# Ethernet.net
KiCad netlist of a schematic drawn in Altium Designer
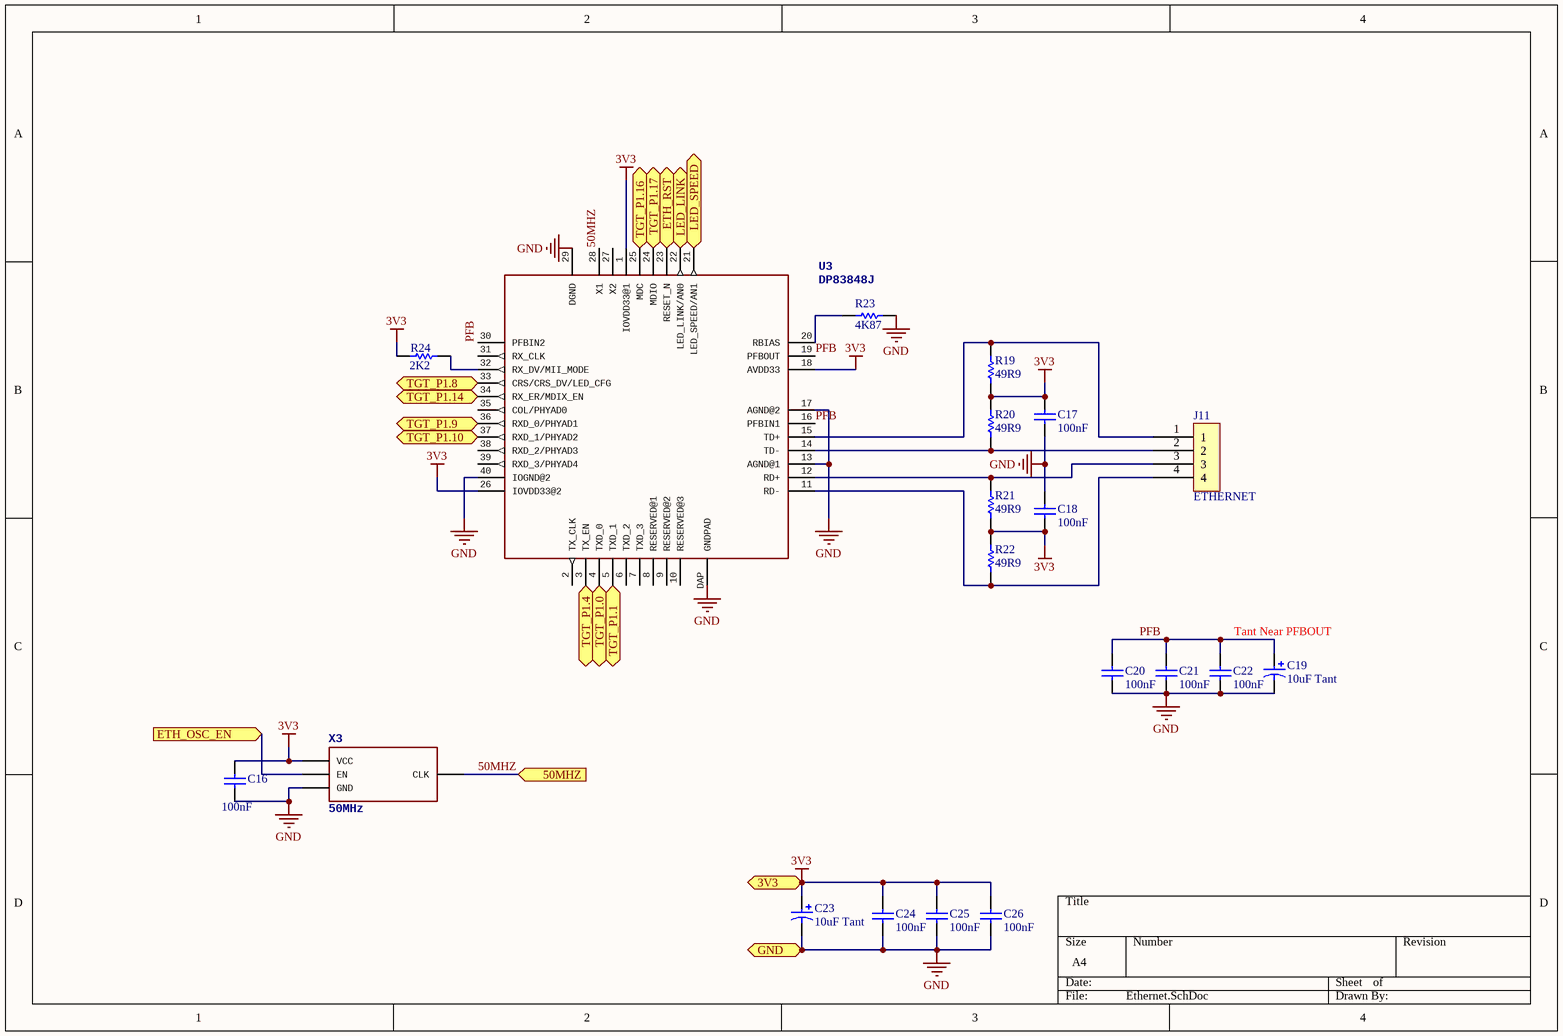
[diagram p0: Ethernet.SchDoc]

(export (version "E")
  (design (tool "Eeschema 10.0.6"))
  (components
    (comp (ref "C16")
      (value "100nF")
      (footprint "CAPC0603(1608)100_L")
      (description "CAP 100nF 6.3V ±5% 0603 (1608 Metric) Thickness 1mm SMD")
      (fields (field (name "TOLERANCE") "Â±5%"))
      (libsource (lib "Altium Content Vault") (part "CMP-1035-02575-1"))
    )
    (comp (ref "C17")
      (value "100nF")
      (footprint "CAPC0603(1608)100_L")
      (description "CAP 100nF 6.3V ±5% 0603 (1608 Metric) Thickness 1mm SMD")
      (fields (field (name "TOLERANCE") "Â±5%"))
      (libsource (lib "Altium Content Vault") (part "CMP-1035-02575-1"))
    )
    (comp (ref "C18")
      (value "100nF")
      (footprint "CAPC0603(1608)100_L")
      (description "CAP 100nF 6.3V ±5% 0603 (1608 Metric) Thickness 1mm SMD")
      (fields (field (name "TOLERANCE") "Â±5%"))
      (libsource (lib "Altium Content Vault") (part "CMP-1035-02575-1"))
    )
    (comp (ref "C19")
      (value "10uF Tant")
      (footprint "CAPMP3528X12N")
      (libsource (lib "passive") (part "cap_pol"))
    )
    (comp (ref "C20")
      (value "100nF")
      (footprint "CAPC0603(1608)100_L")
      (description "CAP 100nF 6.3V ±5% 0603 (1608 Metric) Thickness 1mm SMD")
      (fields (field (name "TOLERANCE") "Â±5%"))
      (libsource (lib "Altium Content Vault") (part "CMP-1035-02575-1"))
    )
    (comp (ref "C21")
      (value "100nF")
      (footprint "CAPC0603(1608)100_L")
      (description "CAP 100nF 6.3V ±5% 0603 (1608 Metric) Thickness 1mm SMD")
      (fields (field (name "TOLERANCE") "Â±5%"))
      (libsource (lib "Altium Content Vault") (part "CMP-1035-02575-1"))
    )
    (comp (ref "C22")
      (value "100nF")
      (footprint "CAPC0603(1608)100_L")
      (description "CAP 100nF 6.3V ±5% 0603 (1608 Metric) Thickness 1mm SMD")
      (fields (field (name "TOLERANCE") "Â±5%"))
      (libsource (lib "Altium Content Vault") (part "CMP-1035-02575-1"))
    )
    (comp (ref "C23")
      (value "10uF Tant")
      (footprint "CAPMP3528X12N")
      (libsource (lib "passive") (part "cap_pol"))
    )
    (comp (ref "C24")
      (value "100nF")
      (footprint "CAPC0603(1608)100_L")
      (description "CAP 100nF 6.3V ±5% 0603 (1608 Metric) Thickness 1mm SMD")
      (fields (field (name "TOLERANCE") "Â±5%"))
      (libsource (lib "Altium Content Vault") (part "CMP-1035-02575-1"))
    )
    (comp (ref "C25")
      (value "100nF")
      (footprint "CAPC0603(1608)100_L")
      (description "CAP 100nF 6.3V ±5% 0603 (1608 Metric) Thickness 1mm SMD")
      (fields (field (name "TOLERANCE") "Â±5%"))
      (libsource (lib "Altium Content Vault") (part "CMP-1035-02575-1"))
    )
    (comp (ref "C26")
      (value "100nF")
      (footprint "CAPC0603(1608)100_L")
      (description "CAP 100nF 6.3V ±5% 0603 (1608 Metric) Thickness 1mm SMD")
      (fields (field (name "TOLERANCE") "Â±5%"))
      (libsource (lib "Altium Content Vault") (part "CMP-1035-02575-1"))
    )
    (comp (ref "J11")
      (value "ETHERNET")
      (footprint "MICRO-MATCH-4")
      (libsource (lib "connectors") (part "HEADER-4"))
    )
    (comp (ref "R19")
      (value "49R9")
      (footprint "RESC0603(1608)_L")
      (description "49R9 0.1W 1% 0603 (1608 Metric)  SMD")
      (fields (field (name "POWER") "0.1 W") (field (name "TOLERANCE") "1 %"))
      (libsource (lib "Altium Content Vault") (part "CMP-1012-00363-1"))
    )
    (comp (ref "R20")
      (value "49R9")
      (footprint "RESC0603(1608)_L")
      (description "49R9 0.1W 1% 0603 (1608 Metric)  SMD")
      (fields (field (name "POWER") "0.1 W") (field (name "TOLERANCE") "1 %"))
      (libsource (lib "Altium Content Vault") (part "CMP-1012-00363-1"))
    )
    (comp (ref "R21")
      (value "49R9")
      (footprint "RESC0603(1608)_L")
      (description "49R9 0.1W 1% 0603 (1608 Metric)  SMD")
      (fields (field (name "POWER") "0.1 W") (field (name "TOLERANCE") "1 %"))
      (libsource (lib "Altium Content Vault") (part "CMP-1012-00363-1"))
    )
    (comp (ref "R22")
      (value "49R9")
      (footprint "RESC0603(1608)_L")
      (description "49R9 0.1W 1% 0603 (1608 Metric)  SMD")
      (fields (field (name "POWER") "0.1 W") (field (name "TOLERANCE") "1 %"))
      (libsource (lib "Altium Content Vault") (part "CMP-1012-00363-1"))
    )
    (comp (ref "R23")
      (value "4K87")
      (footprint "RESC0603(1608)_L")
      (description "4K87 0.1W 1% 0603 (1608 Metric)  SMD")
      (fields (field (name "POWER") "0.1 W") (field (name "TOLERANCE") "1 %"))
      (libsource (lib "Altium Content Vault") (part "CMP-1012-00588-1"))
    )
    (comp (ref "R24")
      (value "2K2")
      (footprint "RESC0603(1608)_L")
      (description "2K2 0.1W 1% 0603 (1608 Metric)  SMD")
      (fields (field (name "TOLERANCE") "1 %") (field (name "POWER") "0.1 W"))
      (libsource (lib "Altium Content Vault") (part "CMP-1012-00546-1"))
    )
    (comp (ref "U3") (value "DP83848J") (footprint "LLP-40") (libsource (lib "mbed-HDK") (part "DP83848J")))
    (comp (ref "X3") (value "50MHz") (footprint "3.2X.2.5") (libsource (lib "mbed-HDK") (part "OSCILLATOR")))
  )
  (nets
    (net (code "1") (name "/50MHZ") (class "Default")
      (node (ref "U3") (pin "28") (pinfunction "X1_28") (pintype "passive"))
      (node (ref "X3") (pin "P$3") (pinfunction "CLK_P$3") (pintype "passive"))
    )
    (net (code "2") (name "/ETH_OSC_EN") (class "Default")
      (node (ref "X3") (pin "P$1") (pinfunction "EN_P$1") (pintype "passive"))
    )
    (net (code "3") (name "/ETH_RST") (class "Default")
      (node (ref "U3") (pin "23") (pinfunction "RESET_N_23") (pintype "passive"))
    )
    (net (code "4") (name "/LED_LINK") (class "Default")
      (node (ref "U3") (pin "22") (pinfunction "LED_LINK/AN0_22") (pintype "output"))
    )
    (net (code "5") (name "/LED_SPEED") (class "Default")
      (node (ref "U3") (pin "21") (pinfunction "LED_SPEED/AN1_21") (pintype "output"))
    )
    (net (code "6") (name "/PFB") (class "Default")
      (node (ref "C19") (pin "2") (pinfunction "2_2") (pintype "passive"))
      (node (ref "C20") (pin "2") (pinfunction "2_2") (pintype "passive"))
      (node (ref "C21") (pin "1") (pinfunction "1_1") (pintype "passive"))
      (node (ref "C22") (pin "1") (pinfunction "1_1") (pintype "passive"))
      (node (ref "U3") (pin "16") (pinfunction "PFBIN1_16") (pintype "passive"))
      (node (ref "U3") (pin "19") (pinfunction "PFBOUT_19") (pintype "passive"))
      (node (ref "U3") (pin "30") (pinfunction "PFBIN2_30") (pintype "passive"))
    )
    (net (code "7") (name "/TGT_P1.0") (class "Default")
      (node (ref "U3") (pin "4") (pinfunction "TXD_0_4") (pintype "passive"))
    )
    (net (code "8") (name "/TGT_P1.1") (class "Default")
      (node (ref "U3") (pin "5") (pinfunction "TXD_1_5") (pintype "passive"))
    )
    (net (code "9") (name "/TGT_P1.4") (class "Default")
      (node (ref "U3") (pin "3") (pinfunction "TX_EN_3") (pintype "passive"))
    )
    (net (code "10") (name "/TGT_P1.8") (class "Default")
      (node (ref "U3") (pin "33") (pinfunction "CRS/CRS_DV/LED_CFG_33") (pintype "output"))
    )
    (net (code "11") (name "/TGT_P1.9") (class "Default")
      (node (ref "U3") (pin "36") (pinfunction "RXD_0/PHYAD1_36") (pintype "output"))
    )
    (net (code "12") (name "/TGT_P1.10") (class "Default")
      (node (ref "U3") (pin "37") (pinfunction "RXD_1/PHYAD2_37") (pintype "output"))
    )
    (net (code "13") (name "/TGT_P1.14") (class "Default")
      (node (ref "U3") (pin "34") (pinfunction "RX_ER/MDIX_EN_34") (pintype "output"))
    )
    (net (code "14") (name "/TGT_P1.16") (class "Default")
      (node (ref "U3") (pin "25") (pinfunction "MDC_25") (pintype "passive"))
    )
    (net (code "15") (name "/TGT_P1.17") (class "Default")
      (node (ref "U3") (pin "24") (pinfunction "MDIO_24") (pintype "passive"))
    )
    (net (code "16") (name "3V3") (class "Default")
      (node (ref "C16") (pin "2") (pinfunction "2_2") (pintype "passive"))
      (node (ref "C17") (pin "2") (pinfunction "2_2") (pintype "passive"))
      (node (ref "C18") (pin "1") (pinfunction "1_1") (pintype "passive"))
      (node (ref "C23") (pin "2") (pinfunction "2_2") (pintype "passive"))
      (node (ref "C24") (pin "2") (pinfunction "2_2") (pintype "passive"))
      (node (ref "C25") (pin "2") (pinfunction "2_2") (pintype "passive"))
      (node (ref "C26") (pin "2") (pinfunction "2_2") (pintype "passive"))
      (node (ref "R19") (pin "1") (pinfunction "1_1") (pintype "passive"))
      (node (ref "R20") (pin "2") (pinfunction "2_2") (pintype "passive"))
      (node (ref "R21") (pin "1") (pinfunction "1_1") (pintype "passive"))
      (node (ref "R22") (pin "2") (pinfunction "2_2") (pintype "passive"))
      (node (ref "R24") (pin "1") (pinfunction "1_1") (pintype "passive"))
      (node (ref "U3") (pin "1") (pinfunction "IOVDD33@1_1") (pintype "power_in"))
      (node (ref "U3") (pin "18") (pinfunction "AVDD33_18") (pintype "power_in"))
      (node (ref "U3") (pin "26") (pinfunction "IOVDD33@2_26") (pintype "power_in"))
      (node (ref "X3") (pin "P$4") (pinfunction "VCC_P$4") (pintype "passive"))
    )
    (net (code "17") (name "GND") (class "Default")
      (node (ref "C16") (pin "1") (pinfunction "1_1") (pintype "passive"))
      (node (ref "C17") (pin "1") (pinfunction "1_1") (pintype "passive"))
      (node (ref "C18") (pin "2") (pinfunction "2_2") (pintype "passive"))
      (node (ref "C19") (pin "1") (pinfunction "1_1") (pintype "passive"))
      (node (ref "C20") (pin "1") (pinfunction "1_1") (pintype "passive"))
      (node (ref "C21") (pin "2") (pinfunction "2_2") (pintype "passive"))
      (node (ref "C22") (pin "2") (pinfunction "2_2") (pintype "passive"))
      (node (ref "C23") (pin "1") (pinfunction "1_1") (pintype "passive"))
      (node (ref "C24") (pin "1") (pinfunction "1_1") (pintype "passive"))
      (node (ref "C25") (pin "1") (pinfunction "1_1") (pintype "passive"))
      (node (ref "C26") (pin "1") (pinfunction "1_1") (pintype "passive"))
      (node (ref "R23") (pin "2") (pinfunction "2_2") (pintype "passive"))
      (node (ref "U3") (pin "13") (pinfunction "AGND@1_13") (pintype "power_in"))
      (node (ref "U3") (pin "17") (pinfunction "AGND@2_17") (pintype "power_in"))
      (node (ref "U3") (pin "29") (pinfunction "DGND_29") (pintype "power_in"))
      (node (ref "U3") (pin "40") (pinfunction "IOGND@2_40") (pintype "power_in"))
      (node (ref "U3") (pin "DAP") (pinfunction "GNDPAD_DAP") (pintype "power_in"))
      (node (ref "X3") (pin "P$2") (pinfunction "GND_P$2") (pintype "passive"))
    )
    (net (code "18") (name "Net-(U3-RBIAS)") (class "Default")
      (node (ref "R23") (pin "1") (pinfunction "1_1") (pintype "passive"))
      (node (ref "U3") (pin "20") (pinfunction "RBIAS_20") (pintype "passive"))
    )
    (net (code "19") (name "Net-(U3-RD+)") (class "Default")
      (node (ref "J11") (pin "3") (pinfunction "3_3") (pintype "passive"))
      (node (ref "R21") (pin "2") (pinfunction "2_2") (pintype "passive"))
      (node (ref "U3") (pin "12") (pinfunction "RD+_12") (pintype "passive"))
    )
    (net (code "20") (name "Net-(U3-RD-)") (class "Default")
      (node (ref "J11") (pin "4") (pinfunction "4_4") (pintype "passive"))
      (node (ref "R22") (pin "1") (pinfunction "1_1") (pintype "passive"))
      (node (ref "U3") (pin "11") (pinfunction "RD-_11") (pintype "passive"))
    )
    (net (code "21") (name "Net-(U3-RX_DV{slash}MII_MODE)") (class "Default")
      (node (ref "R24") (pin "2") (pinfunction "2_2") (pintype "passive"))
      (node (ref "U3") (pin "32") (pinfunction "RX_DV/MII_MODE_32") (pintype "output"))
    )
    (net (code "22") (name "Net-(U3-TD+)") (class "Default")
      (node (ref "J11") (pin "1") (pinfunction "1_1") (pintype "passive"))
      (node (ref "R19") (pin "2") (pinfunction "2_2") (pintype "passive"))
      (node (ref "U3") (pin "15") (pinfunction "TD+_15") (pintype "passive"))
    )
    (net (code "23") (name "Net-(U3-TD-)") (class "Default")
      (node (ref "J11") (pin "2") (pinfunction "2_2") (pintype "passive"))
      (node (ref "R20") (pin "1") (pinfunction "1_1") (pintype "passive"))
      (node (ref "U3") (pin "14") (pinfunction "TD-_14") (pintype "passive"))
    )
    (net (code "24") (name "unconnected-(U3-COL{slash}PHYAD0-Pad35)") (class "Default")
      (node (ref "U3") (pin "35") (pinfunction "COL/PHYAD0_35") (pintype "output"))
    )
    (net (code "25") (name "unconnected-(U3-RESERVED@1-Pad8)") (class "Default")
      (node (ref "U3") (pin "8") (pinfunction "RESERVED@1_8") (pintype "passive"))
    )
    (net (code "26") (name "unconnected-(U3-RESERVED@2-Pad9)") (class "Default")
      (node (ref "U3") (pin "9") (pinfunction "RESERVED@2_9") (pintype "passive"))
    )
    (net (code "27") (name "unconnected-(U3-RESERVED@3-Pad10)") (class "Default")
      (node (ref "U3") (pin "10") (pinfunction "RESERVED@3_10") (pintype "passive"))
    )
    (net (code "28") (name "unconnected-(U3-RXD_2{slash}PHYAD3-Pad38)") (class "Default")
      (node (ref "U3") (pin "38") (pinfunction "RXD_2/PHYAD3_38") (pintype "output"))
    )
    (net (code "29") (name "unconnected-(U3-RXD_3{slash}PHYAD4-Pad39)") (class "Default")
      (node (ref "U3") (pin "39") (pinfunction "RXD_3/PHYAD4_39") (pintype "output"))
    )
    (net (code "30") (name "unconnected-(U3-RX_CLK-Pad31)") (class "Default")
      (node (ref "U3") (pin "31") (pinfunction "RX_CLK_31") (pintype "output"))
    )
    (net (code "31") (name "unconnected-(U3-TXD_2-Pad6)") (class "Default")
      (node (ref "U3") (pin "6") (pinfunction "TXD_2_6") (pintype "passive"))
    )
    (net (code "32") (name "unconnected-(U3-TXD_3-Pad7)") (class "Default")
      (node (ref "U3") (pin "7") (pinfunction "TXD_3_7") (pintype "passive"))
    )
    (net (code "33") (name "unconnected-(U3-TX_CLK-Pad2)") (class "Default")
      (node (ref "U3") (pin "2") (pinfunction "TX_CLK_2") (pintype "output"))
    )
    (net (code "34") (name "unconnected-(U3-X2-Pad27)") (class "Default")
      (node (ref "U3") (pin "27") (pinfunction "X2_27") (pintype "passive"))
    )
  )
)
